# TopLevel.net
KiCad netlist of a schematic drawn in Altium Designer
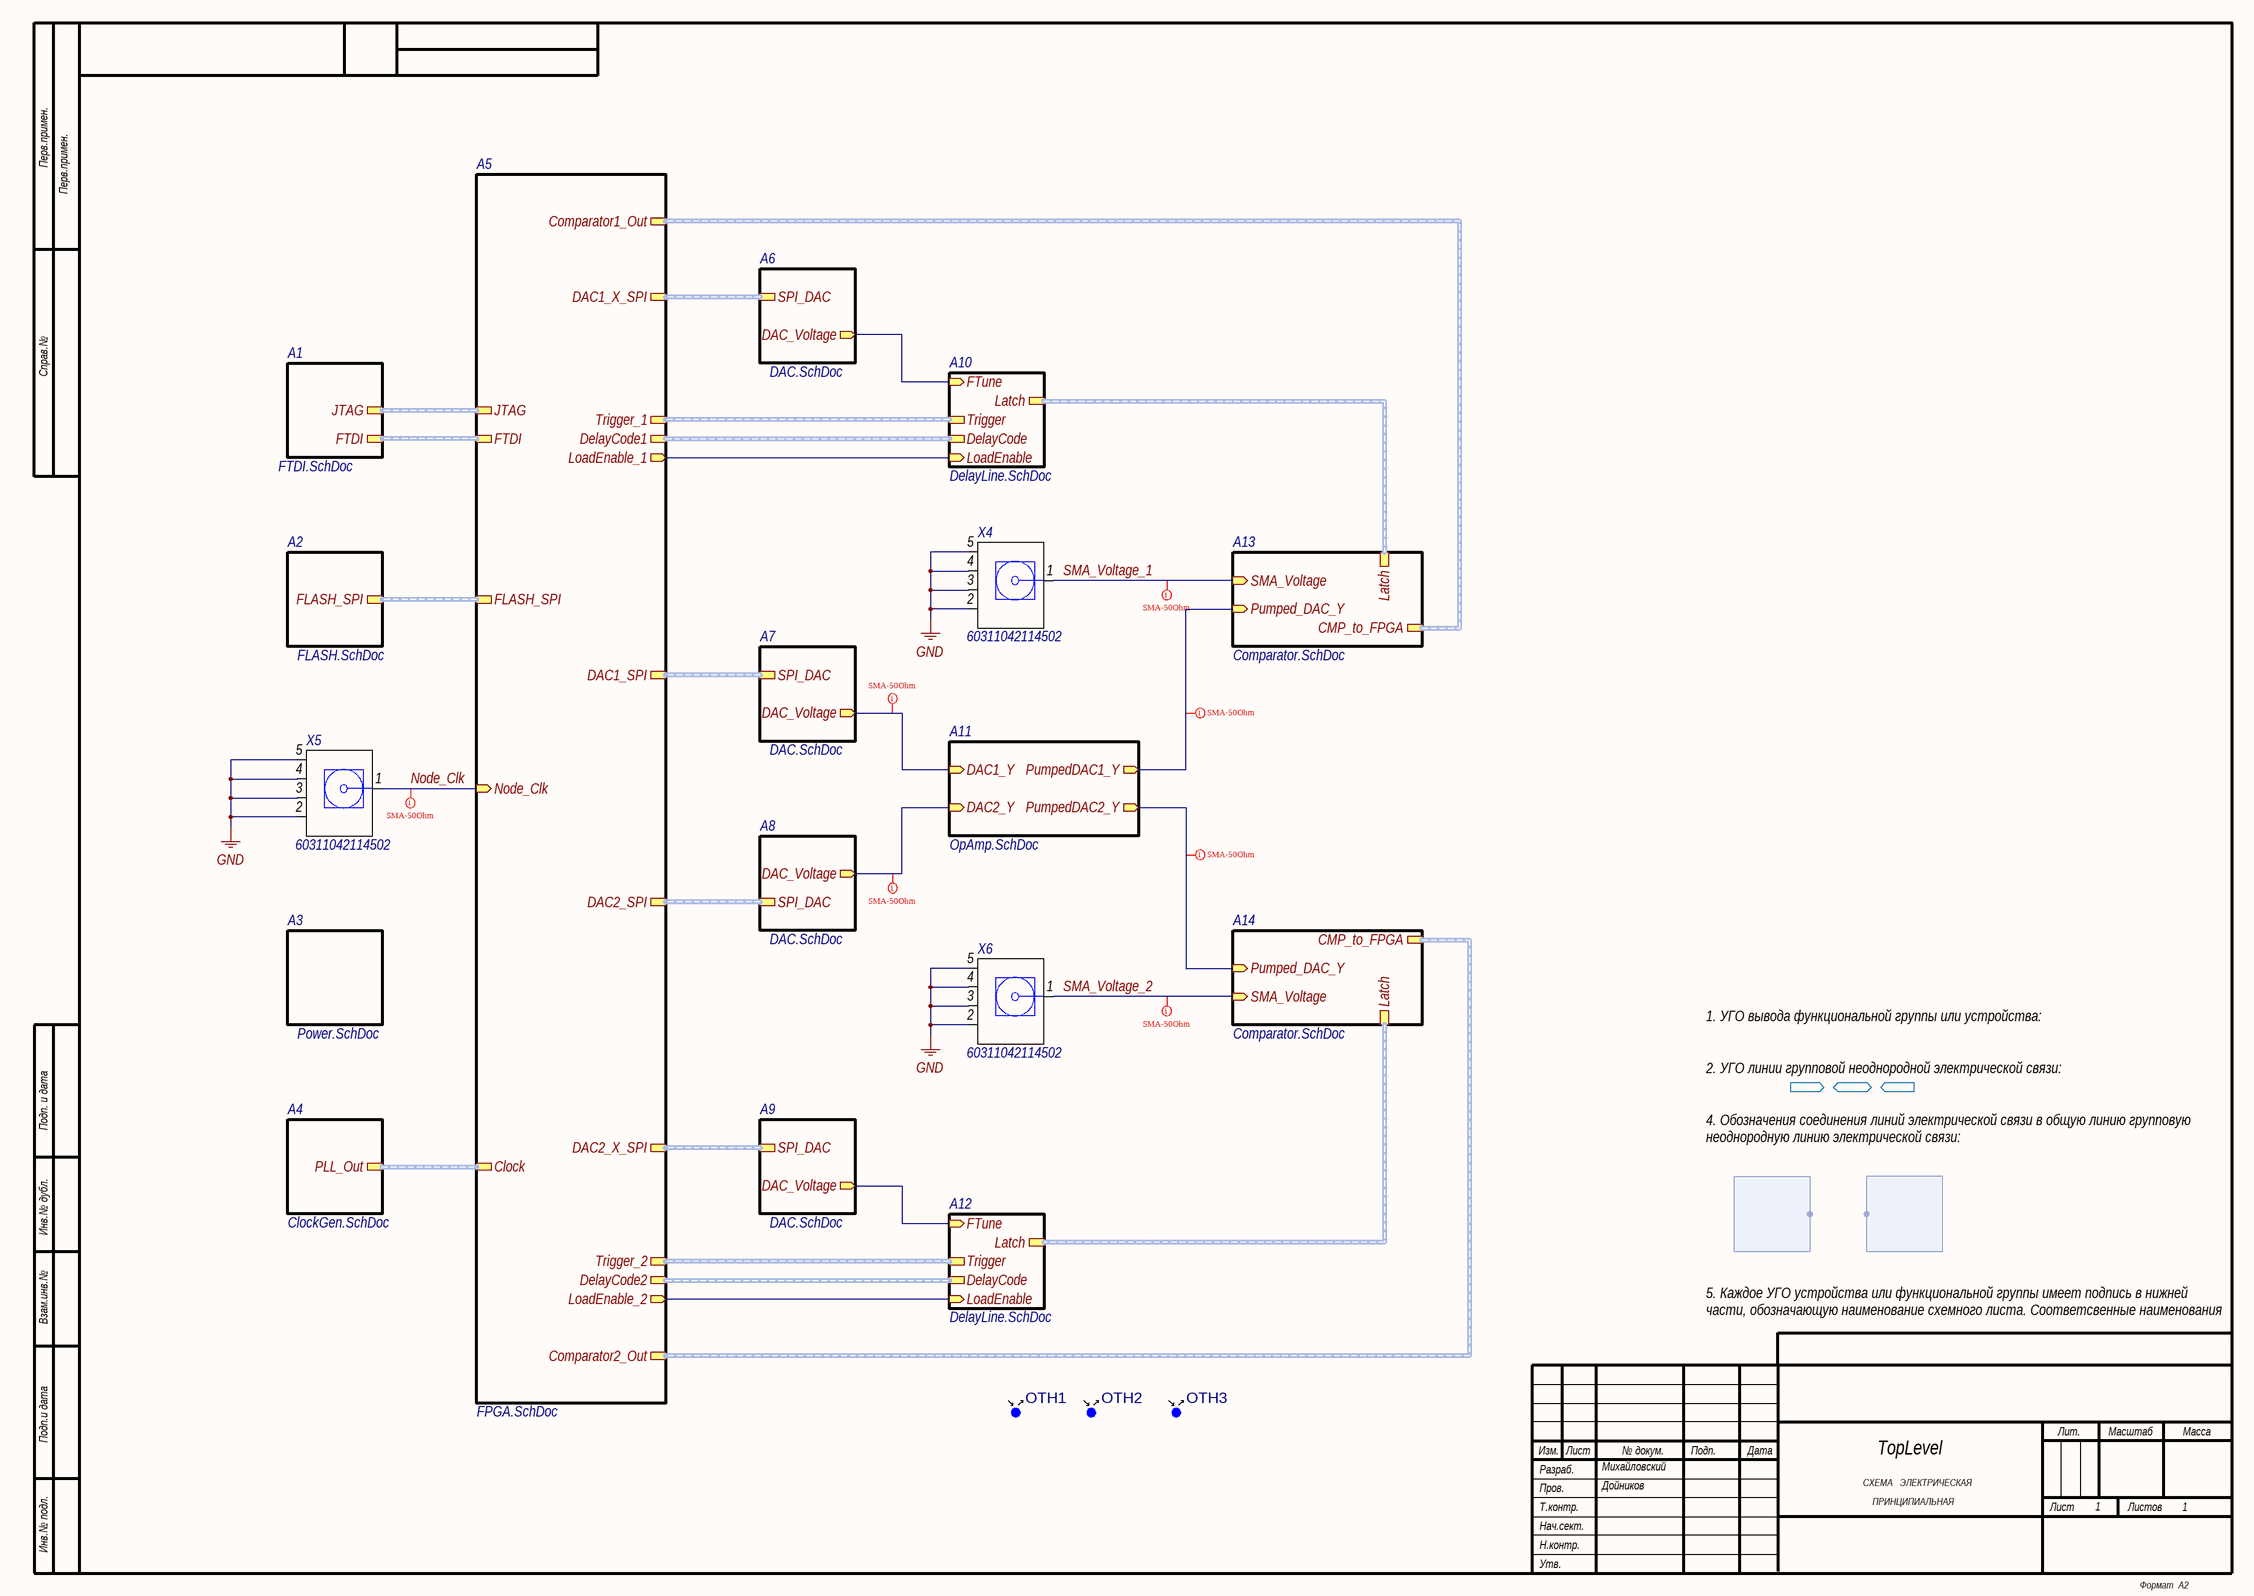
[diagram p0: TopLevel.SchDoc]

(export (version "E")
  (design (tool "Eeschema 10.0.6"))
  (components
    (comp (ref "OTH1")
      (value "REPER_D1.0MM")
      (footprint "REPER_D1.0MM")
      (libsource (lib "Library") (part "REPER_D1.0MM"))
    )
    (comp (ref "OTH2")
      (value "REPER_D1.0MM")
      (footprint "REPER_D1.0MM")
      (libsource (lib "Library") (part "REPER_D1.0MM"))
    )
    (comp (ref "OTH3")
      (value "REPER_D1.0MM")
      (footprint "REPER_D1.0MM")
      (libsource (lib "Library") (part "REPER_D1.0MM"))
    )
    (comp (ref "X4")
      (value "~")
      (footprint "60311042114502")
      (fields
        (field (name "PART NUMBER") "SMA_WR_60311042114502")
        (field (name "MANUFACTURER") "WE")
        (field (name "MPN") "60311042114502")
      )
      (libsource (lib "Library") (part "SMA_WR_60311042114502"))
    )
    (comp (ref "X5")
      (value "~")
      (footprint "60311042114502")
      (fields
        (field (name "PART NUMBER") "SMA_WR_60311042114502")
        (field (name "MANUFACTURER") "WE")
        (field (name "MPN") "60311042114502")
      )
      (libsource (lib "Library") (part "SMA_WR_60311042114502"))
    )
    (comp (ref "X6")
      (value "~")
      (footprint "60311042114502")
      (fields
        (field (name "PART NUMBER") "SMA_WR_60311042114502")
        (field (name "MANUFACTURER") "WE")
        (field (name "MPN") "60311042114502")
      )
      (libsource (lib "Library") (part "SMA_WR_60311042114502"))
    )
  )
  (nets
    (net (code "21") (name "/Node_Clk") (class "Default")
      (node (ref "X5") (pin "1") (pinfunction "Signal_1") (pintype "passive"))
    )
    (net (code "24") (name "/SMA_Voltage_1") (class "Default")
      (node (ref "X4") (pin "1") (pinfunction "Signal_1") (pintype "passive"))
    )
    (net (code "25") (name "/SMA_Voltage_2") (class "Default")
      (node (ref "X6") (pin "1") (pinfunction "Signal_1") (pintype "passive"))
    )
    (net (code "28") (name "GND") (class "Default")
      (node (ref "X4") (pin "2") (pinfunction "GND_2") (pintype "power_in"))
      (node (ref "X4") (pin "3") (pinfunction "GND_3") (pintype "power_in"))
      (node (ref "X4") (pin "4") (pinfunction "GND_4") (pintype "power_in"))
      (node (ref "X4") (pin "5") (pinfunction "GND_5") (pintype "power_in"))
      (node (ref "X5") (pin "2") (pinfunction "GND_2") (pintype "power_in"))
      (node (ref "X5") (pin "3") (pinfunction "GND_3") (pintype "power_in"))
      (node (ref "X5") (pin "4") (pinfunction "GND_4") (pintype "power_in"))
      (node (ref "X5") (pin "5") (pinfunction "GND_5") (pintype "power_in"))
      (node (ref "X6") (pin "2") (pinfunction "GND_2") (pintype "power_in"))
      (node (ref "X6") (pin "3") (pinfunction "GND_3") (pintype "power_in"))
      (node (ref "X6") (pin "4") (pinfunction "GND_4") (pintype "power_in"))
      (node (ref "X6") (pin "5") (pinfunction "GND_5") (pintype "power_in"))
    )
  )
)
